# ece411-t04-filamint-V4_6_1.net
KiCad netlist of a schematic drawn in EAGLE
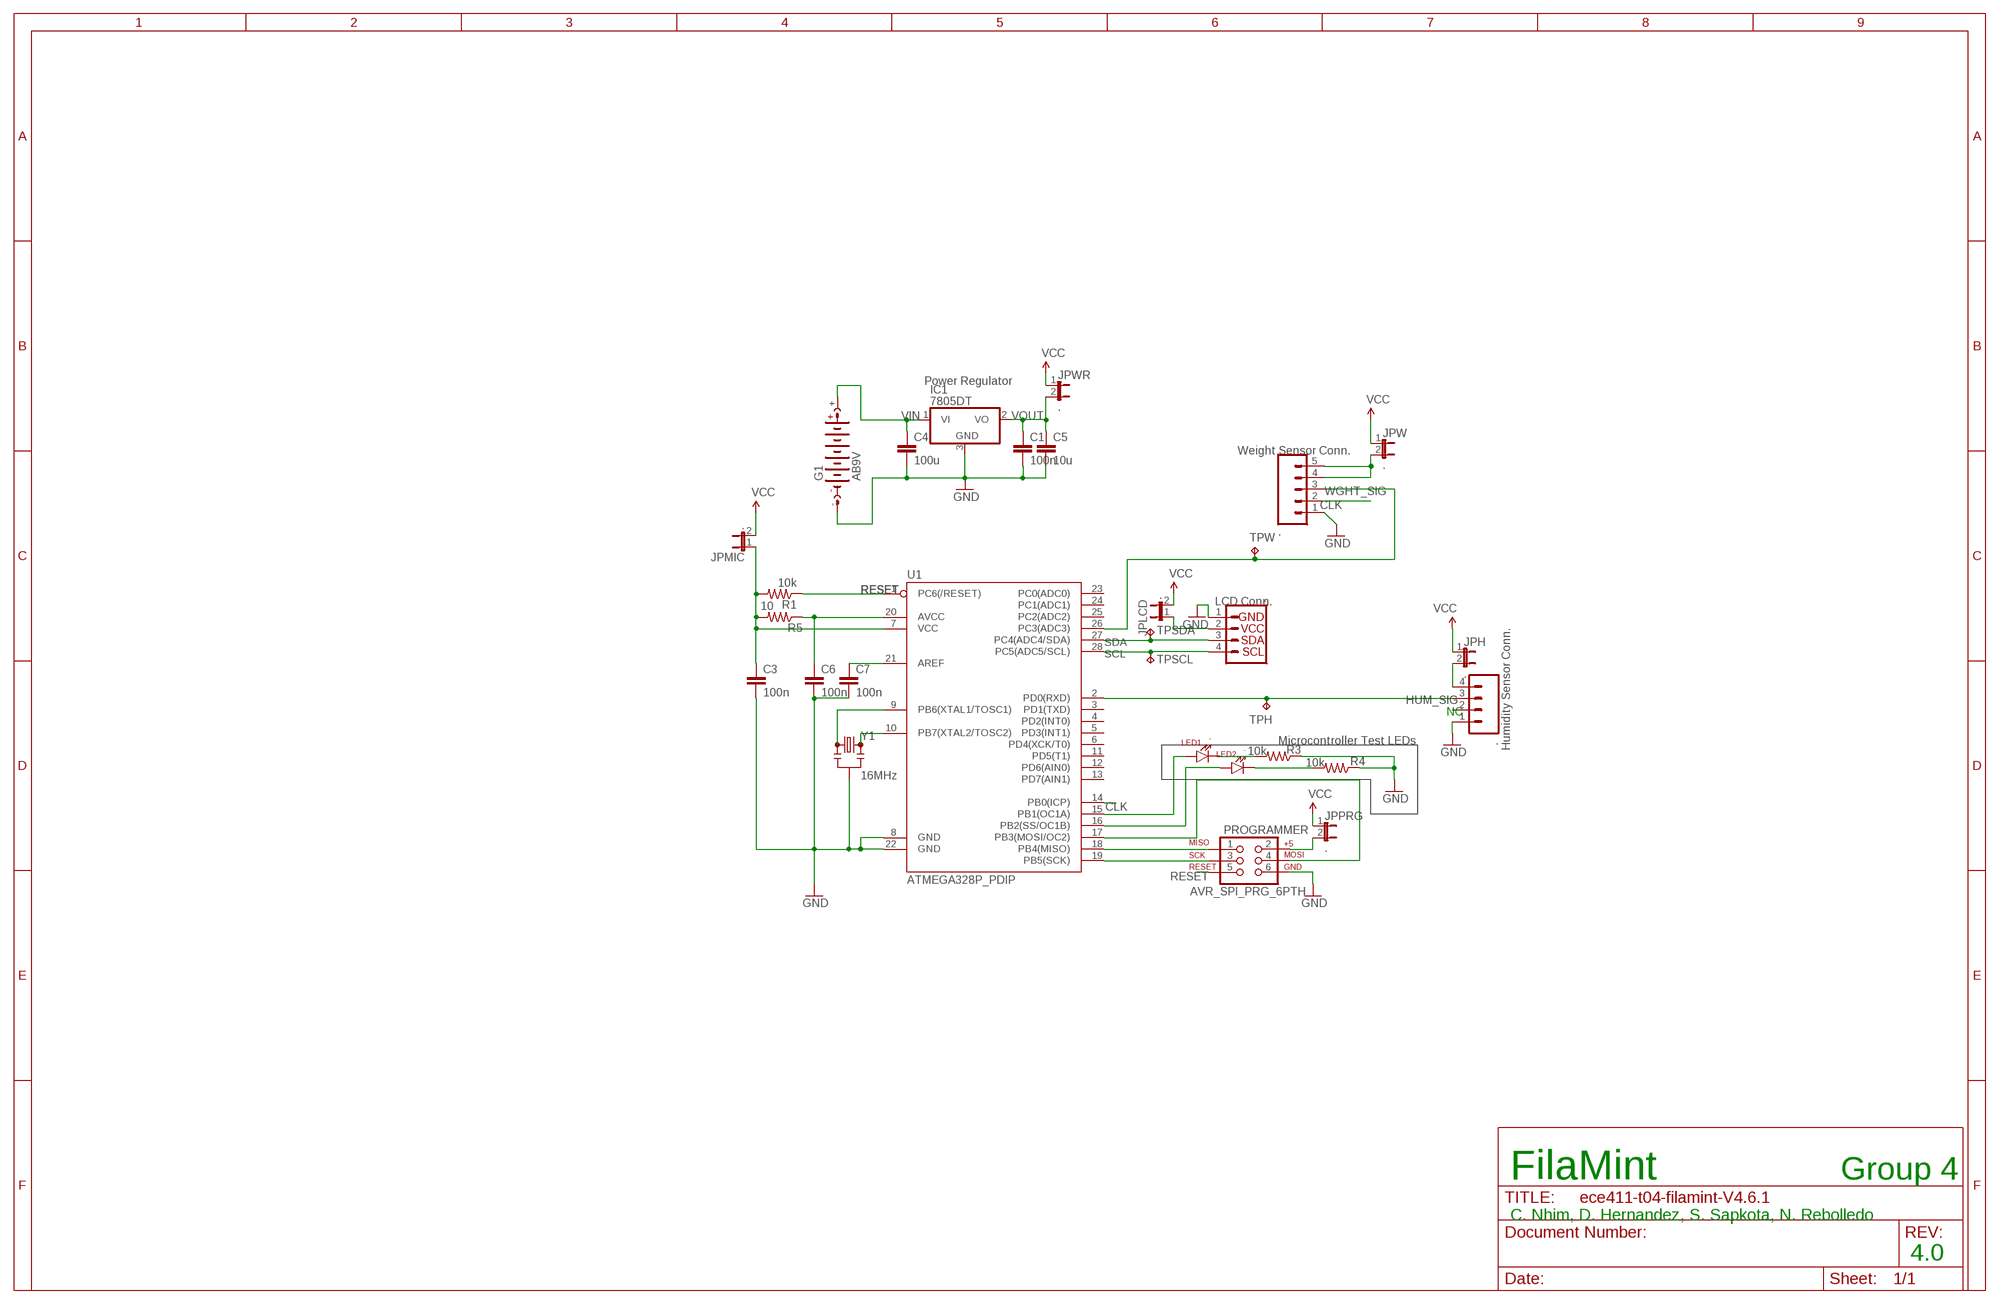
[diagram p0: schematic, sheet 1]

(export (version "E")
  (design (tool "Eeschema 10.0.6"))
  (components
    (comp (ref "C1")
      (value "100n")
      (footprint "eagle-import:C0805")
      (libsource (lib "eagle-import") (part "C-EUC0805"))
    )
    (comp (ref "C3")
      (value "100n")
      (footprint "eagle-import:C0805")
      (libsource (lib "eagle-import") (part "C-EUC0805"))
    )
    (comp (ref "C4")
      (value "100u")
      (footprint "eagle-import:C025-024X044")
      (libsource (lib "eagle-import") (part "C-EU025-024X044"))
    )
    (comp (ref "C5")
      (value "10u")
      (footprint "eagle-import:C025-024X044")
      (libsource (lib "eagle-import") (part "C-EU025-024X044"))
    )
    (comp (ref "C6")
      (value "100n")
      (footprint "eagle-import:C0805")
      (libsource (lib "eagle-import") (part "C-EUC0805"))
    )
    (comp (ref "C7")
      (value "100n")
      (footprint "eagle-import:C0805")
      (libsource (lib "eagle-import") (part "C-EUC0805"))
    )
    (comp (ref "DHT22")
      (value ".")
      (footprint "eagle-import:1X04-1MM-RA")
      (libsource (lib "eagle-import") (part "M04SMD2"))
    )
    (comp (ref "G1")
      (value "AB9V")
      (footprint "eagle-import:AB9V")
      (libsource (lib "eagle-import") (part "AB9V"))
    )
    (comp (ref "HX711")
      (value ".")
      (footprint "eagle-import:1X05-1MM")
      (libsource (lib "eagle-import") (part "M05SMD"))
    )
    (comp (ref "IC1")
      (value "7805DT")
      (footprint "eagle-import:TO252")
      (libsource (lib "eagle-import") (part "78DT05"))
    )
    (comp (ref "JPH")
      (value ".")
      (footprint "eagle-import:JP1")
      (libsource (lib "eagle-import") (part "JP1E"))
    )
    (comp (ref "JPLCD")
      (value ".")
      (footprint "eagle-import:JP1")
      (libsource (lib "eagle-import") (part "JP1E"))
    )
    (comp (ref "JPMIC")
      (value ".")
      (footprint "eagle-import:JP1")
      (libsource (lib "eagle-import") (part "JP1E"))
    )
    (comp (ref "JPPRG")
      (value ".")
      (footprint "eagle-import:JP1")
      (libsource (lib "eagle-import") (part "JP1E"))
    )
    (comp (ref "JPW")
      (value ".")
      (footprint "eagle-import:JP1")
      (libsource (lib "eagle-import") (part "JP1E"))
    )
    (comp (ref "JPWR")
      (value ".")
      (footprint "eagle-import:JP1")
      (libsource (lib "eagle-import") (part "JP1E"))
    )
    (comp (ref "LCD")
      (value ".")
      (footprint "eagle-import:1X04")
      (libsource (lib "eagle-import") (part "I2C_STANDARD"))
    )
    (comp (ref "LED1")
      (value ".")
      (footprint "eagle-import:LTE-302")
      (libsource (lib "eagle-import") (part "LTE-302"))
    )
    (comp (ref "LED2")
      (value ".")
      (footprint "eagle-import:LTE-302")
      (libsource (lib "eagle-import") (part "LTE-302"))
    )
    (comp (ref "PROGRAMMER")
      (value "AVR_SPI_PRG_6PTH")
      (footprint "eagle-import:2X3")
      (libsource (lib "eagle-import") (part "AVR_SPI_PRG_6PTH"))
    )
    (comp (ref "R1")
      (value "10k")
      (footprint "eagle-import:0204_5")
      (libsource (lib "eagle-import") (part "R-US_0204/5"))
    )
    (comp (ref "R3")
      (value "10k")
      (footprint "eagle-import:0204_5")
      (libsource (lib "eagle-import") (part "R-US_0204/5"))
    )
    (comp (ref "R4")
      (value "10k")
      (footprint "eagle-import:0204_5")
      (libsource (lib "eagle-import") (part "R-US_0204/5"))
    )
    (comp (ref "R5")
      (value "10")
      (footprint "eagle-import:0204_5")
      (libsource (lib "eagle-import") (part "R-US_0204/5"))
    )
    (comp (ref "TPH")
      (value "TPB1,27")
      (footprint "eagle-import:B1,27")
      (libsource (lib "eagle-import") (part "TPB1,27"))
    )
    (comp (ref "TPSCL")
      (value "TPB1,27")
      (footprint "eagle-import:B1,27")
      (libsource (lib "eagle-import") (part "TPB1,27"))
    )
    (comp (ref "TPSDA")
      (value "TPB1,27")
      (footprint "eagle-import:B1,27")
      (libsource (lib "eagle-import") (part "TPB1,27"))
    )
    (comp (ref "TPW")
      (value "TPB1,27")
      (footprint "eagle-import:B1,27")
      (libsource (lib "eagle-import") (part "TPB1,27"))
    )
    (comp (ref "U1")
      (value "ATMEGA328P_PDIP")
      (footprint "eagle-import:DIL28-3")
      (libsource (lib "eagle-import") (part "ATMEGA328P_PDIP"))
    )
    (comp (ref "Y1")
      (value "16MHz")
      (footprint "eagle-import:RESONATOR-PTH")
      (libsource (lib "eagle-import") (part "RESONATORPTH"))
    )
  )
  (nets
    (net (code "1") (name "/CLK") (class "Default")
      (node (ref "HX711") (pin "2") (pinfunction "2_2") (pintype "passive"))
      (node (ref "U1") (pin "14") (pinfunction "PB0(ICP)_14") (pintype "bidirectional"))
    )
    (net (code "2") (name "/HUM_SIG") (class "Default")
      (node (ref "DHT22") (pin "3") (pinfunction "3_3") (pintype "passive"))
      (node (ref "TPH") (pin "TP") (pinfunction "TP_TP") (pintype "input"))
      (node (ref "U1") (pin "2") (pinfunction "PD0(RXD)_2") (pintype "bidirectional"))
    )
    (net (code "3") (name "/RESET") (class "Default")
      (node (ref "PROGRAMMER") (pin "5") (pinfunction "5_5") (pintype "passive"))
      (node (ref "R1") (pin "1") (pinfunction "1_1") (pintype "passive"))
      (node (ref "U1") (pin "1") (pinfunction "PC6(/RESET)_1") (pintype "bidirectional"))
    )
    (net (code "4") (name "/SCL") (class "Default")
      (node (ref "LCD") (pin "4") (pinfunction "4_4") (pintype "passive"))
      (node (ref "TPSCL") (pin "TP") (pinfunction "TP_TP") (pintype "input"))
      (node (ref "U1") (pin "28") (pinfunction "PC5(ADC5/SCL)_28") (pintype "bidirectional"))
    )
    (net (code "5") (name "/SDA") (class "Default")
      (node (ref "LCD") (pin "3") (pinfunction "3_3") (pintype "passive"))
      (node (ref "TPSDA") (pin "TP") (pinfunction "TP_TP") (pintype "input"))
      (node (ref "U1") (pin "27") (pinfunction "PC4(ADC4/SDA)_27") (pintype "bidirectional"))
    )
    (net (code "6") (name "/VIN") (class "Default")
      (node (ref "C4") (pin "1") (pinfunction "1_1") (pintype "passive"))
      (node (ref "G1") (pin "+") (pinfunction "+_+") (pintype "passive"))
      (node (ref "IC1") (pin "1") (pinfunction "VI_1") (pintype "input"))
    )
    (net (code "7") (name "/WGHT_SIG") (class "Default")
      (node (ref "HX711") (pin "3") (pinfunction "3_3") (pintype "passive"))
      (node (ref "TPW") (pin "TP") (pinfunction "TP_TP") (pintype "input"))
      (node (ref "U1") (pin "26") (pinfunction "PC3(ADC3)_26") (pintype "bidirectional"))
    )
    (net (code "8") (name "GND") (class "Default")
      (node (ref "C1") (pin "2") (pinfunction "2_2") (pintype "passive"))
      (node (ref "C3") (pin "2") (pinfunction "2_2") (pintype "passive"))
      (node (ref "C4") (pin "2") (pinfunction "2_2") (pintype "passive"))
      (node (ref "C5") (pin "2") (pinfunction "2_2") (pintype "passive"))
      (node (ref "C6") (pin "2") (pinfunction "2_2") (pintype "passive"))
      (node (ref "C7") (pin "2") (pinfunction "2_2") (pintype "passive"))
      (node (ref "DHT22") (pin "1") (pinfunction "1_1") (pintype "passive"))
      (node (ref "G1") (pin "-") (pinfunction "-_-") (pintype "passive"))
      (node (ref "HX711") (pin "1") (pinfunction "1_1") (pintype "passive"))
      (node (ref "IC1") (pin "3") (pinfunction "GND_3") (pintype "passive"))
      (node (ref "LCD") (pin "1") (pinfunction "1_1") (pintype "passive"))
      (node (ref "PROGRAMMER") (pin "6") (pinfunction "6_6") (pintype "passive"))
      (node (ref "R3") (pin "1") (pinfunction "1_1") (pintype "passive"))
      (node (ref "R4") (pin "1") (pinfunction "1_1") (pintype "passive"))
      (node (ref "U1") (pin "22") (pinfunction "GND_22") (pintype "bidirectional"))
      (node (ref "U1") (pin "8") (pinfunction "GND_8") (pintype "bidirectional"))
      (node (ref "Y1") (pin "2") (pinfunction "2_2") (pintype "passive"))
    )
    (net (code "9") (name "Net-(DHT22-Pad4)") (class "Default")
      (node (ref "DHT22") (pin "4") (pinfunction "4_4") (pintype "passive"))
      (node (ref "JPH") (pin "2") (pinfunction "2_2") (pintype "passive"))
    )
    (net (code "10") (name "Net-(HX711-Pad4)") (class "Default")
      (node (ref "HX711") (pin "4") (pinfunction "4_4") (pintype "passive"))
      (node (ref "HX711") (pin "5") (pinfunction "5_5") (pintype "passive"))
      (node (ref "JPW") (pin "2") (pinfunction "2_2") (pintype "passive"))
    )
    (net (code "11") (name "Net-(IC1-VO)") (class "Default")
      (node (ref "C1") (pin "1") (pinfunction "1_1") (pintype "passive"))
      (node (ref "C5") (pin "1") (pinfunction "1_1") (pintype "passive"))
      (node (ref "IC1") (pin "2") (pinfunction "VO_2") (pintype "passive"))
      (node (ref "JPWR") (pin "2") (pinfunction "2_2") (pintype "passive"))
    )
    (net (code "12") (name "Net-(JPLCD-Pad1)") (class "Default")
      (node (ref "JPLCD") (pin "1") (pinfunction "1_1") (pintype "passive"))
      (node (ref "LCD") (pin "2") (pinfunction "2_2") (pintype "passive"))
    )
    (net (code "13") (name "Net-(JPPRG-Pad2)") (class "Default")
      (node (ref "JPPRG") (pin "2") (pinfunction "2_2") (pintype "passive"))
      (node (ref "PROGRAMMER") (pin "2") (pinfunction "2_2") (pintype "passive"))
    )
    (net (code "14") (name "Net-(LED1-PadC)") (class "Default")
      (node (ref "LED1") (pin "C") (pinfunction "C_C") (pintype "bidirectional"))
      (node (ref "R3") (pin "2") (pinfunction "2_2") (pintype "passive"))
    )
    (net (code "15") (name "Net-(LED2-PadC)") (class "Default")
      (node (ref "LED2") (pin "C") (pinfunction "C_C") (pintype "bidirectional"))
      (node (ref "R4") (pin "2") (pinfunction "2_2") (pintype "passive"))
    )
    (net (code "16") (name "Net-(U1-AREF)") (class "Default")
      (node (ref "C7") (pin "1") (pinfunction "1_1") (pintype "passive"))
      (node (ref "U1") (pin "21") (pinfunction "AREF_21") (pintype "bidirectional"))
    )
    (net (code "17") (name "Net-(U1-AVCC)") (class "Default")
      (node (ref "C6") (pin "1") (pinfunction "1_1") (pintype "passive"))
      (node (ref "R5") (pin "1") (pinfunction "1_1") (pintype "passive"))
      (node (ref "U1") (pin "20") (pinfunction "AVCC_20") (pintype "bidirectional"))
    )
    (net (code "18") (name "Net-(U1-PB1(OC1A))") (class "Default")
      (node (ref "LED1") (pin "A") (pinfunction "A_A") (pintype "bidirectional"))
      (node (ref "U1") (pin "15") (pinfunction "PB1(OC1A)_15") (pintype "bidirectional"))
    )
    (net (code "19") (name "Net-(U1-PB2(SS{slash}OC1B))") (class "Default")
      (node (ref "LED2") (pin "A") (pinfunction "A_A") (pintype "bidirectional"))
      (node (ref "U1") (pin "16") (pinfunction "PB2(SS/OC1B)_16") (pintype "bidirectional"))
    )
    (net (code "20") (name "Net-(U1-PB3(MOSI{slash}OC2))") (class "Default")
      (node (ref "PROGRAMMER") (pin "4") (pinfunction "4_4") (pintype "passive"))
      (node (ref "U1") (pin "17") (pinfunction "PB3(MOSI/OC2)_17") (pintype "bidirectional"))
    )
    (net (code "21") (name "Net-(U1-PB4(MISO))") (class "Default")
      (node (ref "PROGRAMMER") (pin "1") (pinfunction "1_1") (pintype "passive"))
      (node (ref "U1") (pin "18") (pinfunction "PB4(MISO)_18") (pintype "bidirectional"))
    )
    (net (code "22") (name "Net-(U1-PB5(SCK))") (class "Default")
      (node (ref "PROGRAMMER") (pin "3") (pinfunction "3_3") (pintype "passive"))
      (node (ref "U1") (pin "19") (pinfunction "PB5(SCK)_19") (pintype "bidirectional"))
    )
    (net (code "23") (name "Net-(U1-PB6(XTAL1{slash}TOSC1))") (class "Default")
      (node (ref "U1") (pin "9") (pinfunction "PB6(XTAL1/TOSC1)_9") (pintype "bidirectional"))
      (node (ref "Y1") (pin "1") (pinfunction "1_1") (pintype "passive"))
    )
    (net (code "24") (name "Net-(U1-PB7(XTAL2{slash}TOSC2))") (class "Default")
      (node (ref "U1") (pin "10") (pinfunction "PB7(XTAL2/TOSC2)_10") (pintype "bidirectional"))
      (node (ref "Y1") (pin "3") (pinfunction "3_3") (pintype "passive"))
    )
    (net (code "25") (name "Net-(U1-VCC)") (class "Default")
      (node (ref "C3") (pin "1") (pinfunction "1_1") (pintype "passive"))
      (node (ref "JPMIC") (pin "1") (pinfunction "1_1") (pintype "passive"))
      (node (ref "R1") (pin "2") (pinfunction "2_2") (pintype "passive"))
      (node (ref "R5") (pin "2") (pinfunction "2_2") (pintype "passive"))
      (node (ref "U1") (pin "7") (pinfunction "VCC_7") (pintype "bidirectional"))
    )
    (net (code "26") (name "VCC") (class "Default")
      (node (ref "JPH") (pin "1") (pinfunction "1_1") (pintype "passive"))
      (node (ref "JPLCD") (pin "2") (pinfunction "2_2") (pintype "passive"))
      (node (ref "JPMIC") (pin "2") (pinfunction "2_2") (pintype "passive"))
      (node (ref "JPPRG") (pin "1") (pinfunction "1_1") (pintype "passive"))
      (node (ref "JPW") (pin "1") (pinfunction "1_1") (pintype "passive"))
      (node (ref "JPWR") (pin "1") (pinfunction "1_1") (pintype "passive"))
    )
    (net (code "27") (name "unconnected-(DHT22-Pad2)") (class "Default")
      (node (ref "DHT22") (pin "2") (pinfunction "2_2") (pintype "passive"))
    )
    (net (code "28") (name "unconnected-(U1-PC0(ADC0)-Pad23)") (class "Default")
      (node (ref "U1") (pin "23") (pinfunction "PC0(ADC0)_23") (pintype "bidirectional"))
    )
    (net (code "29") (name "unconnected-(U1-PC1(ADC1)-Pad24)") (class "Default")
      (node (ref "U1") (pin "24") (pinfunction "PC1(ADC1)_24") (pintype "bidirectional"))
    )
    (net (code "30") (name "unconnected-(U1-PC2(ADC2)-Pad25)") (class "Default")
      (node (ref "U1") (pin "25") (pinfunction "PC2(ADC2)_25") (pintype "bidirectional"))
    )
    (net (code "31") (name "unconnected-(U1-PD1(TXD)-Pad3)") (class "Default")
      (node (ref "U1") (pin "3") (pinfunction "PD1(TXD)_3") (pintype "bidirectional"))
    )
    (net (code "32") (name "unconnected-(U1-PD2(INT0)-Pad4)") (class "Default")
      (node (ref "U1") (pin "4") (pinfunction "PD2(INT0)_4") (pintype "bidirectional"))
    )
    (net (code "33") (name "unconnected-(U1-PD3(INT1)-Pad5)") (class "Default")
      (node (ref "U1") (pin "5") (pinfunction "PD3(INT1)_5") (pintype "bidirectional"))
    )
    (net (code "34") (name "unconnected-(U1-PD4(XCK{slash}T0)-Pad6)") (class "Default")
      (node (ref "U1") (pin "6") (pinfunction "PD4(XCK/T0)_6") (pintype "bidirectional"))
    )
    (net (code "35") (name "unconnected-(U1-PD5(T1)-Pad11)") (class "Default")
      (node (ref "U1") (pin "11") (pinfunction "PD5(T1)_11") (pintype "bidirectional"))
    )
    (net (code "36") (name "unconnected-(U1-PD6(AIN0)-Pad12)") (class "Default")
      (node (ref "U1") (pin "12") (pinfunction "PD6(AIN0)_12") (pintype "bidirectional"))
    )
    (net (code "37") (name "unconnected-(U1-PD7(AIN1)-Pad13)") (class "Default")
      (node (ref "U1") (pin "13") (pinfunction "PD7(AIN1)_13") (pintype "bidirectional"))
    )
  )
)
